# SCHEMATIC_EasyEDA.net
KiCad netlist of a schematic drawn in EasyEDA
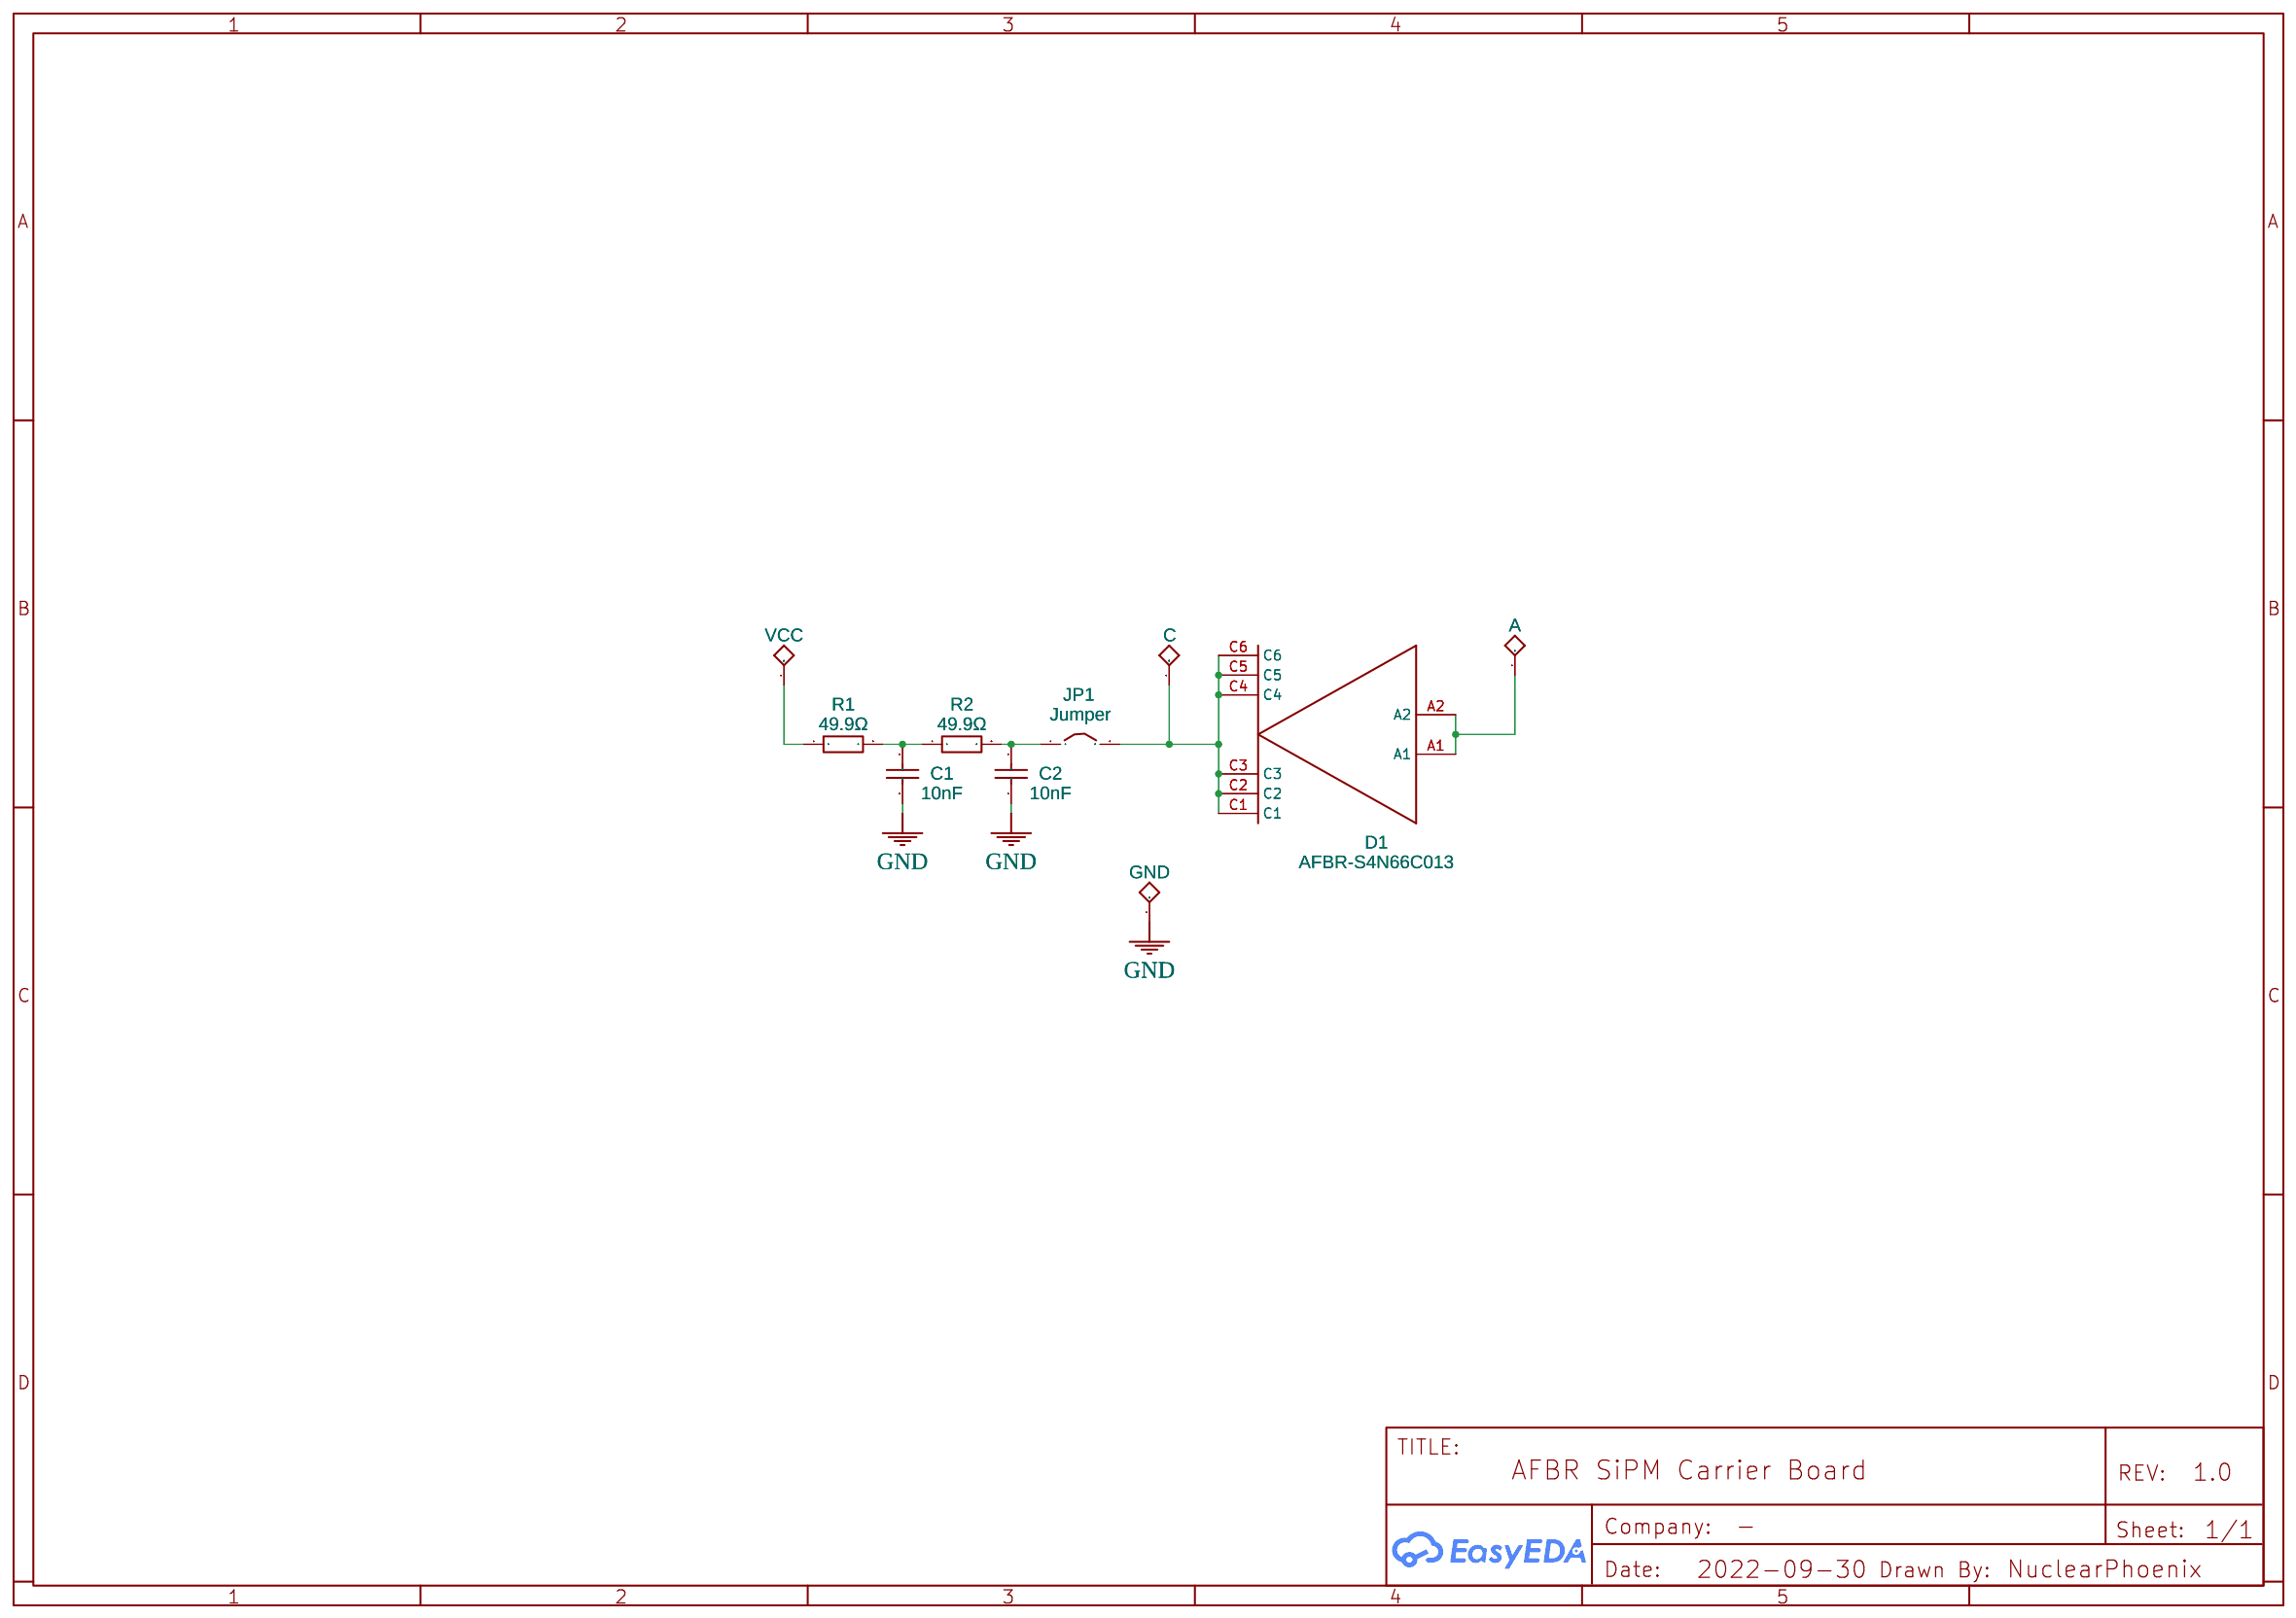
[diagram p0: schematic sheet]

(export (version "E")
  (design (tool "Eeschema 10.0.6"))
  (components
    (comp (ref "A") (value "OUT") (libsource (lib "") (part "TEST_POINT-RND-.100_3")))
    (comp (ref "C") (value "VCC") (libsource (lib "") (part "TEST_POINT-RND-.100_2")))
    (comp (ref "C1")
      (value "10nF")
      (fields
        (field (name "BOM_Manufacturer Part") "CL21B103KBANNNC")
        (field (name "BOM_Supplier Part") "C1710")
      )
      (libsource (lib "") (part "CL21B103KBANNNC"))
    )
    (comp (ref "C2")
      (value "10nF")
      (fields
        (field (name "BOM_Manufacturer Part") "CL21B103KBANNNC")
        (field (name "BOM_Supplier Part") "C1710")
      )
      (libsource (lib "") (part "CL21B103KBANNNC"))
    )
    (comp (ref "D1")
      (value "AFBR-S4N66C013")
      (fields (field (name "BOM_Supplier Part") "630-AFBR-S4N66C013"))
      (libsource (lib "") (part "AFBR-S4N66C013"))
    )
    (comp (ref "GND") (value "VCC") (libsource (lib "") (part "TEST_POINT-RND-.100_1")))
    (comp (ref "JP1")
      (value "Jumper")
      (fields
        (field (name "BOM_Manufacturer Part") "0603WAF0000T5E")
        (field (name "BOM_Supplier Part") "C21189")
      )
      (libsource (lib "") (part "Jumper Solder bridge"))
    )
    (comp (ref "R1")
      (value "49.9Ω")
      (fields
        (field (name "BOM_Manufacturer Part") "0805W8F499JT5E")
        (field (name "BOM_Supplier Part") "C17720")
      )
      (libsource (lib "") (part "0805W8F499JT5E"))
    )
    (comp (ref "R2")
      (value "49.9Ω")
      (fields
        (field (name "BOM_Manufacturer Part") "0805W8F499JT5E")
        (field (name "BOM_Supplier Part") "C17720")
      )
      (libsource (lib "") (part "0805W8F499JT5E"))
    )
    (comp (ref "VCC") (value "VCC") (libsource (lib "") (part "TEST_POINT-RND-.100")))
  )
  (nets
    (net (code "1") (name "GND") (class "Default")
      (node (ref "C1") (pin "1") (pinfunction "1_1") (pintype "input"))
      (node (ref "C2") (pin "1") (pinfunction "1_1") (pintype "input"))
      (node (ref "GND") (pin "1") (pinfunction "PIN_1") (pintype "bidirectional"))
    )
    (net (code "2") (name "Net-(A-PIN)") (class "Default")
      (node (ref "A") (pin "1") (pinfunction "PIN_1") (pintype "bidirectional"))
      (node (ref "D1") (pin "A1") (pinfunction "A1_A1") (pintype "unspecified"))
      (node (ref "D1") (pin "A2") (pinfunction "A2_A2") (pintype "unspecified"))
    )
    (net (code "3") (name "Net-(C-PIN)") (class "Default")
      (node (ref "C") (pin "1") (pinfunction "PIN_1") (pintype "bidirectional"))
      (node (ref "D1") (pin "C1") (pinfunction "C1_C1") (pintype "unspecified"))
      (node (ref "D1") (pin "C2") (pinfunction "C2_C2") (pintype "unspecified"))
      (node (ref "D1") (pin "C3") (pinfunction "C3_C3") (pintype "unspecified"))
      (node (ref "D1") (pin "C4") (pinfunction "C4_C4") (pintype "unspecified"))
      (node (ref "D1") (pin "C5") (pinfunction "C5_C5") (pintype "unspecified"))
      (node (ref "D1") (pin "C6") (pinfunction "C6_C6") (pintype "unspecified"))
      (node (ref "JP1") (pin "2") (pinfunction "2_2") (pintype "input"))
    )
    (net (code "4") (name "Net-(C1-Pad2)") (class "Default")
      (node (ref "C1") (pin "2") (pinfunction "2_2") (pintype "input"))
      (node (ref "R1") (pin "2") (pinfunction "2_2") (pintype "input"))
      (node (ref "R2") (pin "1") (pinfunction "1_1") (pintype "input"))
    )
    (net (code "5") (name "Net-(C2-Pad2)") (class "Default")
      (node (ref "C2") (pin "2") (pinfunction "2_2") (pintype "input"))
      (node (ref "JP1") (pin "1") (pinfunction "1_1") (pintype "input"))
      (node (ref "R2") (pin "2") (pinfunction "2_2") (pintype "input"))
    )
    (net (code "6") (name "Net-(VCC-PIN)") (class "Default")
      (node (ref "R1") (pin "1") (pinfunction "1_1") (pintype "input"))
      (node (ref "VCC") (pin "1") (pinfunction "PIN_1") (pintype "bidirectional"))
    )
  )
)
